# Sheet1.net
KiCad netlist of a schematic drawn in Altium Designer
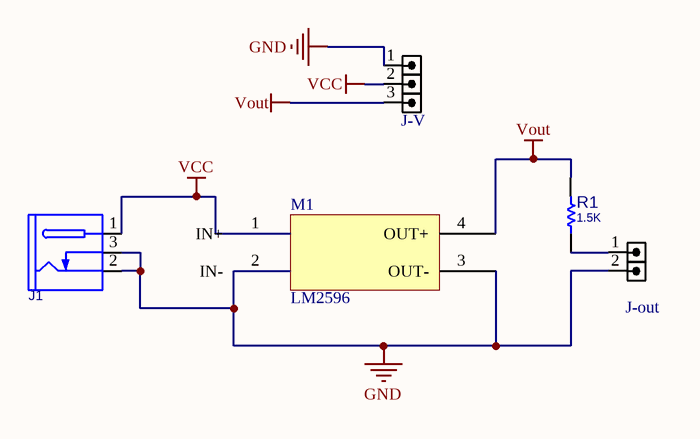
[diagram p0: Sheet1.SchDoc]

(export (version "E")
  (design (tool "Eeschema 10.0.6"))
  (components
    (comp (ref "J-out")
      (value "HDRM2")
      (footprint "HDR_M_1X2")
      (description "CONN, HEADER, Male, pitch: 2.54mm, 2POS")
      (libsource (lib "conn_header_2.54mm_st") (part "HDR_M_1X2"))
    )
    (comp (ref "J-V")
      (value "HDRM3")
      (footprint "HDR_M_1X3")
      (description "CONN, HEADER, Male, pitch: 2.54mm, 3POS")
      (libsource (lib "conn_header_2.54mm_st") (part "HDR_M_1X3"))
    )
    (comp (ref "J1")
      (value "DC_POWER_JACK")
      (footprint "JAC_PWR2")
      (description "CONN, PWR JACK DC, PLUG DIAM 2.0MM RA THD")
      (fields
        (field (name "MANF") "CUI STACK")
        (field (name "MANF_P#") "PJ-202A, PJ-002AH, PJ-102AH, KLDX-0202")
      )
      (libsource (lib "conn_powerJack") (part "CONN_PWR_JACKR2"))
    )
    (comp (ref "M1")
      (value "LM2596")
      (footprint "dc-dc-module")
      (description "step-down voltage")
      (libsource (lib "Schlib1") (part "MADOULE-DC-DC"))
    )
    (comp (ref "R1")
      (value "1.5K")
      (footprint "R025W_AX04")
      (description "RESISTOR, THD")
      (fields (field (name "MANF_P#") "RK73H1ETTP4701F") (field (name "MANF") "KOA SPEER"))
      (libsource (lib "passive_thd") (part "RES_THD"))
    )
  )
  (nets
    (net (code "1") (name "GND") (class "Default")
      (node (ref "J-V") (pin "1") (pinfunction "1_1") (pintype "passive"))
      (node (ref "J-out") (pin "2") (pinfunction "2_2") (pintype "passive"))
      (node (ref "J1") (pin "2") (pinfunction "SLEEVE_2") (pintype "power_in"))
      (node (ref "J1") (pin "3") (pinfunction "INSERTION_DET_3") (pintype "power_in"))
      (node (ref "M1") (pin "2") (pinfunction "IN-_2") (pintype "passive"))
      (node (ref "M1") (pin "3") (pinfunction "OUT-_3") (pintype "passive"))
    )
    (net (code "2") (name "Net-(J-out-Pad1)") (class "Default")
      (node (ref "J-out") (pin "1") (pinfunction "1_1") (pintype "passive"))
      (node (ref "R1") (pin "1") (pinfunction "1_1") (pintype "passive"))
    )
    (net (code "3") (name "VCC") (class "Default")
      (node (ref "J-V") (pin "2") (pinfunction "2_2") (pintype "passive"))
      (node (ref "J1") (pin "1") (pinfunction "TIP_1") (pintype "power_in"))
      (node (ref "M1") (pin "1") (pinfunction "IN+_1") (pintype "passive"))
    )
    (net (code "4") (name "Vout") (class "Default")
      (node (ref "J-V") (pin "3") (pinfunction "3_3") (pintype "passive"))
      (node (ref "M1") (pin "4") (pinfunction "OUT+_4") (pintype "passive"))
      (node (ref "R1") (pin "2") (pinfunction "2_2") (pintype "passive"))
    )
  )
)
